# TL431_OverVoltProt.net
KiCad netlist of a schematic drawn in EAGLE
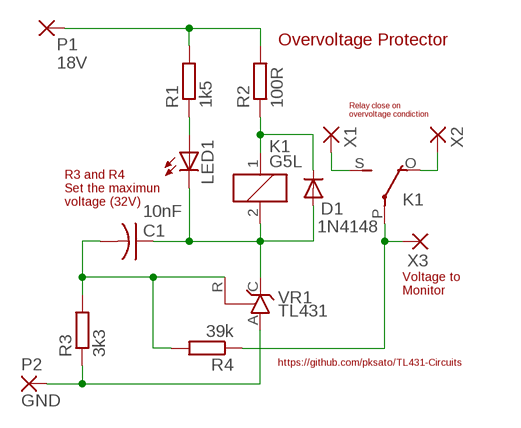
[diagram p0: schematic, sheet 1]

(export (version "E")
  (design (tool "Eeschema 10.0.6"))
  (components
    (comp (ref "C1")
      (value "10nF")
      (footprint "eagle-import:C050-024X044")
      (libsource (lib "eagle-import") (part "C-US050-024X044"))
    )
    (comp (ref "D1")
      (value "1N4148")
      (footprint "eagle-import:D-5")
      (libsource (lib "eagle-import") (part "DIODE-D-5"))
    )
    (comp (ref "K1")
      (value "G5L")
      (footprint "eagle-import:G5LE")
      (libsource (lib "eagle-import") (part "G5L"))
    )
    (comp (ref "LED1")
      (value "LED5MM")
      (footprint "eagle-import:LED5MM")
      (libsource (lib "eagle-import") (part "LED5MM"))
    )
    (comp (ref "P1")
      (value "18V")
      (footprint "eagle-import:2,54_1,0")
      (libsource (lib "eagle-import") (part "WIREPAD2,54/1,0"))
    )
    (comp (ref "P2")
      (value "GND")
      (footprint "eagle-import:2,54_1,0")
      (libsource (lib "eagle-import") (part "WIREPAD2,54/1,0"))
    )
    (comp (ref "R1")
      (value "1k5")
      (footprint "eagle-import:0207_10")
      (libsource (lib "eagle-import") (part "R-EU_0207/10"))
    )
    (comp (ref "R2")
      (value "100R")
      (footprint "eagle-import:0207_10")
      (libsource (lib "eagle-import") (part "R-EU_0207/10"))
    )
    (comp (ref "R3")
      (value "3k3")
      (footprint "eagle-import:0207_10")
      (libsource (lib "eagle-import") (part "R-EU_0207/10"))
    )
    (comp (ref "R4")
      (value "39k")
      (footprint "eagle-import:0207_10")
      (libsource (lib "eagle-import") (part "R-EU_0207/10"))
    )
    (comp (ref "VR1")
      (value "TL431")
      (footprint "eagle-import:TO92-CLP")
      (libsource (lib "eagle-import") (part "TL431CLP"))
    )
    (comp (ref "X1")
      (value "WIREPAD2,54/1,0")
      (footprint "eagle-import:2,54_1,0")
      (libsource (lib "eagle-import") (part "WIREPAD2,54/1,0"))
    )
    (comp (ref "X2")
      (value "WIREPAD2,54/1,0")
      (footprint "eagle-import:2,54_1,0")
      (libsource (lib "eagle-import") (part "WIREPAD2,54/1,0"))
    )
    (comp (ref "X3")
      (value "WIREPAD2,54/1,0")
      (footprint "eagle-import:2,54_1,0")
      (libsource (lib "eagle-import") (part "WIREPAD2,54/1,0"))
    )
  )
  (nets
    (net (code "1") (name "Net-(C1-Pad2)") (class "Default")
      (node (ref "C1") (pin "2") (pinfunction "2_2") (pintype "passive"))
      (node (ref "R3") (pin "2") (pinfunction "2_2") (pintype "passive"))
      (node (ref "R4") (pin "2") (pinfunction "2_2") (pintype "passive"))
      (node (ref "VR1") (pin "R") (pinfunction "R_R") (pintype "passive"))
    )
    (net (code "2") (name "Net-(D1-PadC)") (class "Default")
      (node (ref "D1") (pin "C") (pinfunction "C_C") (pintype "passive"))
      (node (ref "K1") (pin "1") (pinfunction "1_1") (pintype "passive"))
      (node (ref "R2") (pin "1") (pinfunction "1_1") (pintype "passive"))
    )
    (net (code "3") (name "Net-(LED1-C)") (class "Default")
      (node (ref "C1") (pin "1") (pinfunction "1_1") (pintype "passive"))
      (node (ref "D1") (pin "A") (pinfunction "A_A") (pintype "passive"))
      (node (ref "K1") (pin "2") (pinfunction "2_2") (pintype "passive"))
      (node (ref "LED1") (pin "K") (pinfunction "C_K") (pintype "passive"))
      (node (ref "VR1") (pin "C") (pinfunction "C_C") (pintype "passive"))
    )
    (net (code "4") (name "Net-(LED1-PadA)") (class "Default")
      (node (ref "LED1") (pin "A") (pinfunction "A_A") (pintype "passive"))
      (node (ref "R1") (pin "1") (pinfunction "1_1") (pintype "passive"))
    )
    (net (code "5") (name "Net-(P1-P)") (class "Default")
      (node (ref "P1") (pin "1") (pinfunction "P_1") (pintype "passive"))
      (node (ref "R1") (pin "2") (pinfunction "2_2") (pintype "passive"))
      (node (ref "R2") (pin "2") (pinfunction "2_2") (pintype "passive"))
    )
    (net (code "6") (name "Net-(P2-P)") (class "Default")
      (node (ref "P2") (pin "1") (pinfunction "P_1") (pintype "passive"))
      (node (ref "R3") (pin "1") (pinfunction "1_1") (pintype "passive"))
      (node (ref "VR1") (pin "A") (pinfunction "A_A") (pintype "passive"))
    )
    (net (code "7") (name "Net-(X1-P)") (class "Default")
      (node (ref "K1") (pin "S") (pinfunction "S_S") (pintype "passive"))
      (node (ref "X1") (pin "1") (pinfunction "P_1") (pintype "passive"))
    )
    (net (code "8") (name "Net-(X2-P)") (class "Default")
      (node (ref "K1") (pin "O") (pinfunction "O_O") (pintype "passive"))
      (node (ref "X2") (pin "1") (pinfunction "P_1") (pintype "passive"))
    )
    (net (code "9") (name "Net-(X3-P)") (class "Default")
      (node (ref "K1") (pin "P") (pinfunction "P_P") (pintype "passive"))
      (node (ref "R4") (pin "1") (pinfunction "1_1") (pintype "passive"))
      (node (ref "X3") (pin "1") (pinfunction "P_1") (pintype "passive"))
    )
  )
)
